# SolderingStation_Control_-_PUMD2.net
KiCad netlist of a schematic drawn in Altium Designer
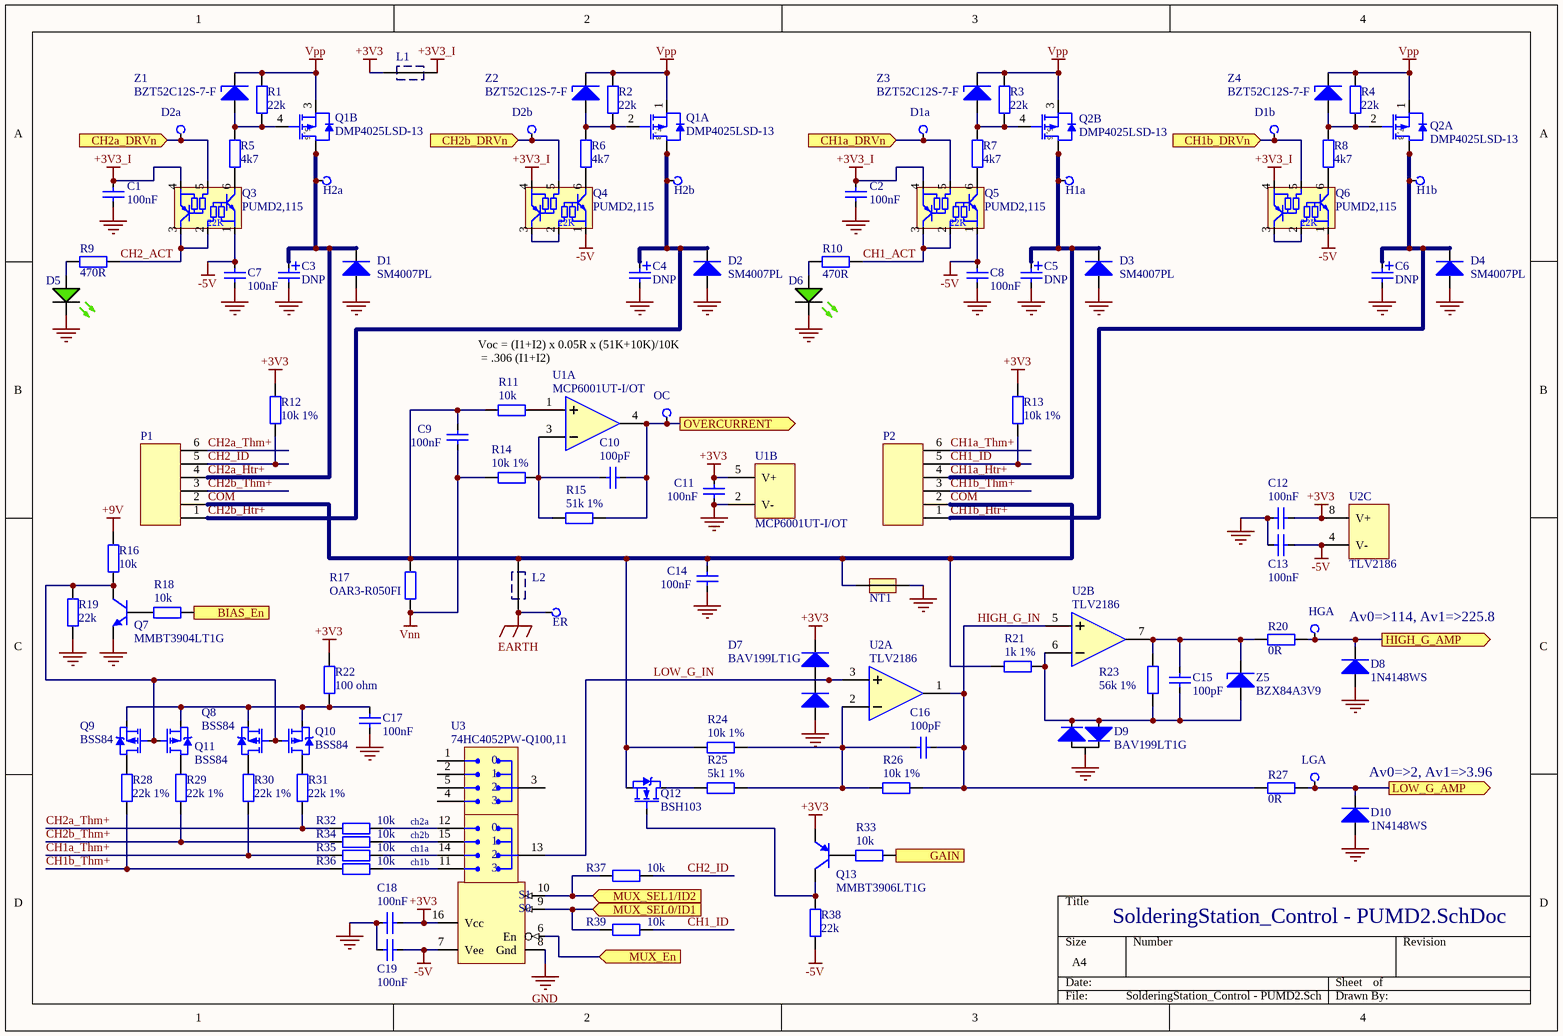
[diagram p0: SolderingStation_Control - PUMD2.SchDoc]

(export (version "E")
  (design (tool "Eeschema 10.0.6"))
  (components
    (comp (ref "C1")
      (value "100nF")
      (footprint "CCNP1608-0603")
      (description "Capacitor non-polar SMT 0603")
      (fields
        (field (name "MANUFACTURER") "Generic Components")
        (field (name "PUBLISHER") "Altium Hobart Technology Centre")
      )
      (libsource (lib "MyLibrary") (part "Cap_CCNP_0603"))
    )
    (comp (ref "C2")
      (value "100nF")
      (footprint "CCNP1608-0603")
      (description "Capacitor non-polar SMT 0603")
      (fields
        (field (name "MANUFACTURER") "Generic Components")
        (field (name "PUBLISHER") "Altium Hobart Technology Centre")
      )
      (libsource (lib "MyLibrary") (part "Cap_CCNP_0603"))
    )
    (comp (ref "C3")
      (value "DNP")
      (footprint "CC2012-0805")
      (description "Capacitor SMT 0805")
      (fields
        (field (name "MANUFACTURER") "Generic Components")
        (field (name "PUBLISHER") "Altium Hobart Technology Centre")
      )
      (libsource (lib "MyLibrary") (part "Cap_CC_0805"))
    )
    (comp (ref "C4")
      (value "DNP")
      (footprint "CC2012-0805")
      (description "Capacitor SMT 0805")
      (fields
        (field (name "MANUFACTURER") "Generic Components")
        (field (name "PUBLISHER") "Altium Hobart Technology Centre")
      )
      (libsource (lib "MyLibrary") (part "Cap_CC_0805"))
    )
    (comp (ref "C5")
      (value "DNP")
      (footprint "CC2012-0805")
      (description "Capacitor SMT 0805")
      (fields
        (field (name "MANUFACTURER") "Generic Components")
        (field (name "PUBLISHER") "Altium Hobart Technology Centre")
      )
      (libsource (lib "MyLibrary") (part "Cap_CC_0805"))
    )
    (comp (ref "C6")
      (value "DNP")
      (footprint "CC2012-0805")
      (description "Capacitor SMT 0805")
      (fields
        (field (name "MANUFACTURER") "Generic Components")
        (field (name "PUBLISHER") "Altium Hobart Technology Centre")
      )
      (libsource (lib "MyLibrary") (part "Cap_CC_0805"))
    )
    (comp (ref "C7")
      (value "100nF")
      (footprint "CCNP1608-0603")
      (description "Capacitor non-polar SMT 0603")
      (fields
        (field (name "MANUFACTURER") "Generic Components")
        (field (name "PUBLISHER") "Altium Hobart Technology Centre")
      )
      (libsource (lib "MyLibrary") (part "Cap_CCNP_0603"))
    )
    (comp (ref "C8")
      (value "100nF")
      (footprint "CCNP1608-0603")
      (description "Capacitor non-polar SMT 0603")
      (fields
        (field (name "MANUFACTURER") "Generic Components")
        (field (name "PUBLISHER") "Altium Hobart Technology Centre")
      )
      (libsource (lib "MyLibrary") (part "Cap_CCNP_0603"))
    )
    (comp (ref "C9")
      (value "100nF")
      (footprint "CCNP1608-0603")
      (description "Capacitor non-polar SMT 0603")
      (fields
        (field (name "MANUFACTURER") "Generic Components")
        (field (name "PUBLISHER") "Altium Hobart Technology Centre")
      )
      (libsource (lib "MyLibrary") (part "Cap_CCNP_0603"))
    )
    (comp (ref "C10")
      (value "100pF")
      (footprint "CCNP1608-0603")
      (description "Capacitor non-polar SMT 0603")
      (fields
        (field (name "MANUFACTURER") "Generic Components")
        (field (name "PUBLISHER") "Altium Hobart Technology Centre")
      )
      (libsource (lib "MyLibrary") (part "Cap_CCNP_0603"))
    )
    (comp (ref "C11")
      (value "100nF")
      (footprint "CCNP1608-0603")
      (description "Capacitor non-polar SMT 0603")
      (fields
        (field (name "MANUFACTURER") "Generic Components")
        (field (name "PUBLISHER") "Altium Hobart Technology Centre")
      )
      (libsource (lib "MyLibrary") (part "Cap_CCNP_0603"))
    )
    (comp (ref "C12")
      (value "100nF")
      (footprint "CCNP1608-0603")
      (description "Capacitor non-polar SMT 0603")
      (fields
        (field (name "MANUFACTURER") "Generic Components")
        (field (name "PUBLISHER") "Altium Hobart Technology Centre")
      )
      (libsource (lib "MyLibrary") (part "Cap_CCNP_0603"))
    )
    (comp (ref "C13")
      (value "100nF")
      (footprint "CCNP1608-0603")
      (description "Capacitor non-polar SMT 0603")
      (fields
        (field (name "MANUFACTURER") "Generic Components")
        (field (name "PUBLISHER") "Altium Hobart Technology Centre")
      )
      (libsource (lib "MyLibrary") (part "Cap_CCNP_0603"))
    )
    (comp (ref "C14")
      (value "100nF")
      (footprint "CCNP1608-0603")
      (description "Capacitor non-polar SMT 0603")
      (fields
        (field (name "MANUFACTURER") "Generic Components")
        (field (name "PUBLISHER") "Altium Hobart Technology Centre")
      )
      (libsource (lib "MyLibrary") (part "Cap_CCNP_0603"))
    )
    (comp (ref "C15")
      (value "100pF")
      (footprint "CCNP1608-0603")
      (description "Capacitor non-polar SMT 0603")
      (fields
        (field (name "MANUFACTURER") "Generic Components")
        (field (name "PUBLISHER") "Altium Hobart Technology Centre")
      )
      (libsource (lib "MyLibrary") (part "Cap_CCNP_0603"))
    )
    (comp (ref "C16")
      (value "100pF")
      (footprint "CCNP1608-0603")
      (description "Capacitor non-polar SMT 0603")
      (fields
        (field (name "MANUFACTURER") "Generic Components")
        (field (name "PUBLISHER") "Altium Hobart Technology Centre")
      )
      (libsource (lib "MyLibrary") (part "Cap_CCNP_0603"))
    )
    (comp (ref "C17")
      (value "100nF")
      (footprint "CCNP1608-0603")
      (description "Capacitor non-polar SMT 0603")
      (fields
        (field (name "MANUFACTURER") "Generic Components")
        (field (name "PUBLISHER") "Altium Hobart Technology Centre")
      )
      (libsource (lib "MyLibrary") (part "Cap_CCNP_0603"))
    )
    (comp (ref "C18")
      (value "100nF")
      (footprint "CCNP1608-0603")
      (description "Capacitor non-polar SMT 0603")
      (fields
        (field (name "MANUFACTURER") "Generic Components")
        (field (name "PUBLISHER") "Altium Hobart Technology Centre")
      )
      (libsource (lib "MyLibrary") (part "Cap_CCNP_0603"))
    )
    (comp (ref "C19")
      (value "100nF")
      (footprint "CCNP1608-0603")
      (description "Capacitor non-polar SMT 0603")
      (fields
        (field (name "MANUFACTURER") "Generic Components")
        (field (name "PUBLISHER") "Altium Hobart Technology Centre")
      )
      (libsource (lib "MyLibrary") (part "Cap_CCNP_0603"))
    )
    (comp (ref "D1")
      (value "SM4007PL")
      (footprint "SOD-123FL")
      (description "Diodes - General Purpose, 1kV 1A 1.1V 1A SOD-123FL")
      (libsource (lib "MyLibrary") (part "SM4007PL"))
    )
    (comp (ref "D1a")
      (value "Drive1")
      (footprint "PCBPIN - 0.7mm")
      (description "Test Point")
      (libsource (lib "MyLibrary") (part "TP"))
    )
    (comp (ref "D1b")
      (value "Drive2")
      (footprint "PCBPIN - 0.7mm")
      (description "Test Point")
      (libsource (lib "MyLibrary") (part "TP"))
    )
    (comp (ref "D2")
      (value "SM4007PL")
      (footprint "SOD-123FL")
      (description "Diodes - General Purpose, 1kV 1A 1.1V 1A SOD-123FL")
      (libsource (lib "MyLibrary") (part "SM4007PL"))
    )
    (comp (ref "D2a")
      (value "Drive2")
      (footprint "PCBPIN - 0.7mm")
      (description "Test Point")
      (libsource (lib "MyLibrary") (part "TP"))
    )
    (comp (ref "D2b")
      (value "Drive2")
      (footprint "PCBPIN - 0.7mm")
      (description "Test Point")
      (libsource (lib "MyLibrary") (part "TP"))
    )
    (comp (ref "D3")
      (value "SM4007PL")
      (footprint "SOD-123FL")
      (description "Diodes - General Purpose, 1kV 1A 1.1V 1A SOD-123FL")
      (libsource (lib "MyLibrary") (part "SM4007PL"))
    )
    (comp (ref "D4")
      (value "SM4007PL")
      (footprint "SOD-123FL")
      (description "Diodes - General Purpose, 1kV 1A 1.1V 1A SOD-123FL")
      (libsource (lib "MyLibrary") (part "SM4007PL"))
    )
    (comp (ref "D5")
      (value "LED")
      (footprint "LED3MM-GREEN - 10mm Proud")
      (description "3mm Green LED")
      (fields (field (name "MANUFACTURER") "Generic Components") (field (name "PUBLISHER") "Altium Limited"))
      (libsource (lib "MySchLib") (part "LED_3MM_GREEN"))
    )
    (comp (ref "D6")
      (value "LED")
      (footprint "LED3MM-GREEN - 10mm Proud")
      (description "3mm Green LED")
      (fields (field (name "MANUFACTURER") "Generic Components") (field (name "PUBLISHER") "Altium Limited"))
      (libsource (lib "MySchLib") (part "LED_3MM_GREEN"))
    )
    (comp (ref "D7")
      (value "BAV199LT1G")
      (footprint "SOT23_M")
      (description "Dual Series low-leakage switching diodes, 3-Pin SOT-23")
      (libsource (lib "MySchLib") (part "BAV199LT1G"))
    )
    (comp (ref "D8")
      (value "1N4148WS")
      (footprint "SOD-323")
      (description "Switching Diode 100V 150mA 1.25V@150mA 4ns SOD-323")
      (libsource (lib "MyLibrary") (part "1N4148WS"))
    )
    (comp (ref "D9")
      (value "BAV199LT1G")
      (footprint "SOT23_M")
      (description "Dual Series low-leakage switching diodes, 3-Pin SOT-23")
      (libsource (lib "MyLibrary") (part "BAV199LT1G"))
    )
    (comp (ref "D10")
      (value "1N4148WS")
      (footprint "SOD-323")
      (description "Switching Diode 100V 150mA 1.25V@150mA 4ns SOD-323")
      (libsource (lib "MyLibrary") (part "1N4148WS"))
    )
    (comp (ref "ER")
      (value "Gnd")
      (footprint "PCBPIN - 1mm")
      (description "Test Point")
      (libsource (lib "") (part "TP_1"))
    )
    (comp (ref "H1a")
      (value "Heater1")
      (footprint "PCBPIN - 0.7mm")
      (description "Test Point")
      (libsource (lib "") (part "TP_1"))
    )
    (comp (ref "H1b")
      (value "Heater2")
      (footprint "PCBPIN - 0.7mm")
      (description "Test Point")
      (libsource (lib "") (part "TP_1"))
    )
    (comp (ref "H2a")
      (value "Heater2")
      (footprint "PCBPIN - 0.7mm")
      (description "Test Point")
      (libsource (lib "") (part "TP_1"))
    )
    (comp (ref "H2b")
      (value "Heater2")
      (footprint "PCBPIN - 0.7mm")
      (description "Test Point")
      (libsource (lib "") (part "TP_1"))
    )
    (comp (ref "HGA")
      (value "TC1")
      (footprint "PCBPIN - 0.7mm")
      (description "Test Point")
      (libsource (lib "MyLibrary") (part "TP"))
    )
    (comp (ref "L1")
      (value "Ferrite Bead")
      (footprint "FB2012-0805")
      (description "Ferrite Bead SMT 0805, TDK MPZ2012S102AT, 0.15OHM, 1.5A")
      (libsource (lib "MySchLib") (part "Ferrite Bead 0805"))
    )
    (comp (ref "L2")
      (value "Ferrite Bead")
      (footprint "FB2012-0805")
      (description "Ferrite Bead SMT 0805, TDK MPZ2012S102AT, 0.15OHM, 1.5A")
      (libsource (lib "MySchLib") (part "Ferrite Bead 0805"))
    )
    (comp (ref "LGA")
      (value "NTC1")
      (footprint "PCBPIN - 0.7mm")
      (description "Test Point")
      (libsource (lib "MyLibrary") (part "TP"))
    )
    (comp (ref "NT1")
      (value "NetTieVia")
      (footprint "NetTieVia")
      (libsource (lib "MyLibrary") (part "NetTieVia"))
    )
    (comp (ref "OC")
      (value "Overcurrent")
      (footprint "PCBPIN - 0.7mm")
      (description "Test Point")
      (libsource (lib "MyLibrary") (part "TP"))
    )
    (comp (ref "P1")
      (value "MOLEX-43045-0612")
      (footprint "MOLEX-43045-0612")
      (description "Wire-To-Board Connector, With Polarizing Peg, 3 mm, 6 Contacts, Header, Micro-Fit 3.0 43045 Series")
      (libsource (lib "MySchLib") (part "MOLEX-43045-0612"))
    )
    (comp (ref "P2")
      (value "MOLEX-43045-0612")
      (footprint "MOLEX-43045-0612")
      (description "Wire-To-Board Connector, With Polarizing Peg, 3 mm, 6 Contacts, Header, Micro-Fit 3.0 43045 Series")
      (libsource (lib "MySchLib") (part "MOLEX-43045-0612"))
    )
    (comp (ref "Q1")
      (value "DMP4025LSD-13")
      (footprint "SO-8_M")
      (description "P-Channel dual MOSFET, 40 V, 7.6 A, 0.018 ohm, SOIC, Surface Mount")
      (libsource (lib "MyLibrary") (part "DMP4025LSD-13"))
    )
    (comp (ref "Q2")
      (value "DMP4025LSD-13")
      (footprint "SO-8_M")
      (description "P-Channel dual MOSFET, 40 V, 7.6 A, 0.018 ohm, SOIC, Surface Mount")
      (libsource (lib "MyLibrary") (part "DMP4025LSD-13"))
    )
    (comp (ref "Q3")
      (value "PUMD2,115")
      (footprint "SOT363-6M")
      (description "Pre-Biased NPN and PNP pair, 50 V, 100 mA, 22 kohm, 22 kohm")
      (libsource (lib "MySchLib") (part "PUMD2,115"))
    )
    (comp (ref "Q4")
      (value "PUMD2,115")
      (footprint "SOT363-6M")
      (description "Pre-Biased NPN and PNP pair, 50 V, 100 mA, 22 kohm, 22 kohm")
      (libsource (lib "MySchLib") (part "PUMD2,115"))
    )
    (comp (ref "Q5")
      (value "PUMD2,115")
      (footprint "SOT363-6M")
      (description "Pre-Biased NPN and PNP pair, 50 V, 100 mA, 22 kohm, 22 kohm")
      (libsource (lib "MySchLib") (part "PUMD2,115"))
    )
    (comp (ref "Q6")
      (value "PUMD2,115")
      (footprint "SOT363-6M")
      (description "Pre-Biased NPN and PNP pair, 50 V, 100 mA, 22 kohm, 22 kohm")
      (libsource (lib "MySchLib") (part "PUMD2,115"))
    )
    (comp (ref "Q7")
      (value "MMBT3904LT1G")
      (footprint "SOT23_N")
      (description "General Purpose Transistor, NPN Silicon, 3-Pin SOT-23, Pb-Free, Tape and Reel")
      (fields (field (name "MANUFACTURER") "On Semiconductor"))
      (libsource (lib "MyLibrary") (part "MMBT3904LT1G"))
    )
    (comp (ref "Q8")
      (value "BSS84")
      (footprint "SOT23_M")
      (description "P-Channel Enhancement Mode FET -0.13 A, -50 V,  RDS(ON) = 10R at VGS = -5 V")
      (libsource (lib "MySchLib") (part "BSS84"))
    )
    (comp (ref "Q9")
      (value "BSS84")
      (footprint "SOT23_M")
      (description "P-Channel Enhancement Mode FET -0.13 A, -50 V,  RDS(ON) = 10R at VGS = -5 V")
      (libsource (lib "MySchLib") (part "BSS84"))
    )
    (comp (ref "Q10")
      (value "BSS84")
      (footprint "SOT23_M")
      (description "P-Channel Enhancement Mode FET -0.13 A, -50 V,  RDS(ON) = 10R at VGS = -5 V")
      (libsource (lib "MySchLib") (part "BSS84"))
    )
    (comp (ref "Q11")
      (value "BSS84")
      (footprint "SOT23_M")
      (description "P-Channel Enhancement Mode FET -0.13 A, -50 V,  RDS(ON) = 10R at VGS = -5 V")
      (libsource (lib "MySchLib") (part "BSS84"))
    )
    (comp (ref "Q12")
      (value "BSH103")
      (footprint "SOT23_N")
      (description "N-channel enhancement mode FET, , 30 V, 850 mA, 0.4 ohm, SOT23")
      (libsource (lib "MyLibrary") (part "BSH103"))
    )
    (comp (ref "Q13")
      (value "MMBT3906LT1G")
      (footprint "SOT23_N")
      (description "General Purpose Transistor, PNP Silicon, 3-Pin SOT-23, Pb-Free, Tape and Reel")
      (fields (field (name "MANUFACTURER") "On Semiconductor"))
      (libsource (lib "MyLibrary") (part "MMBT3906LT1G"))
    )
    (comp (ref "R1")
      (value "22k")
      (footprint "CR1608-0603_N")
      (description "Resistor SMT 0603")
      (fields
        (field (name "MANUFACTURER") "Generic Components")
        (field (name "PUBLISHER") "Altium Hobart Technology Centre")
      )
      (libsource (lib "MyLibrary") (part "Res_CR0603"))
    )
    (comp (ref "R2")
      (value "22k")
      (footprint "CR1608-0603_N")
      (description "Resistor SMT 0603")
      (fields
        (field (name "MANUFACTURER") "Generic Components")
        (field (name "PUBLISHER") "Altium Hobart Technology Centre")
      )
      (libsource (lib "MyLibrary") (part "Res_CR0603"))
    )
    (comp (ref "R3")
      (value "22k")
      (footprint "CR1608-0603_N")
      (description "Resistor SMT 0603")
      (fields
        (field (name "MANUFACTURER") "Generic Components")
        (field (name "PUBLISHER") "Altium Hobart Technology Centre")
      )
      (libsource (lib "MyLibrary") (part "Res_CR0603"))
    )
    (comp (ref "R4")
      (value "22k")
      (footprint "CR1608-0603_N")
      (description "Resistor SMT 0603")
      (fields
        (field (name "MANUFACTURER") "Generic Components")
        (field (name "PUBLISHER") "Altium Hobart Technology Centre")
      )
      (libsource (lib "MyLibrary") (part "Res_CR0603"))
    )
    (comp (ref "R5")
      (value "4k7")
      (footprint "CR1608-0603_N")
      (description "Resistor SMT 0603")
      (fields
        (field (name "MANUFACTURER") "Generic Components")
        (field (name "PUBLISHER") "Altium Hobart Technology Centre")
      )
      (libsource (lib "MyLibrary") (part "Res_CR0603"))
    )
    (comp (ref "R6")
      (value "4k7")
      (footprint "CR1608-0603_N")
      (description "Resistor SMT 0603")
      (fields
        (field (name "MANUFACTURER") "Generic Components")
        (field (name "PUBLISHER") "Altium Hobart Technology Centre")
      )
      (libsource (lib "MyLibrary") (part "Res_CR0603"))
    )
    (comp (ref "R7")
      (value "4k7")
      (footprint "CR1608-0603_N")
      (description "Resistor SMT 0603")
      (fields
        (field (name "MANUFACTURER") "Generic Components")
        (field (name "PUBLISHER") "Altium Hobart Technology Centre")
      )
      (libsource (lib "MyLibrary") (part "Res_CR0603"))
    )
    (comp (ref "R8")
      (value "4k7")
      (footprint "CR1608-0603_N")
      (description "Resistor SMT 0603")
      (fields
        (field (name "MANUFACTURER") "Generic Components")
        (field (name "PUBLISHER") "Altium Hobart Technology Centre")
      )
      (libsource (lib "MyLibrary") (part "Res_CR0603"))
    )
    (comp (ref "R9")
      (value "470R")
      (footprint "CR1608-0603_N")
      (description "Resistor SMT 0603")
      (fields
        (field (name "MANUFACTURER") "Generic Components")
        (field (name "PUBLISHER") "Altium Hobart Technology Centre")
      )
      (libsource (lib "") (part "Res_CR0603_3"))
    )
    (comp (ref "R10")
      (value "470R")
      (footprint "CR1608-0603_N")
      (description "Resistor SMT 0603")
      (fields
        (field (name "MANUFACTURER") "Generic Components")
        (field (name "PUBLISHER") "Altium Hobart Technology Centre")
      )
      (libsource (lib "") (part "Res_CR0603_3"))
    )
    (comp (ref "R11")
      (value "10k")
      (footprint "CR1608-0603_N")
      (description "Resistor SMT 0603")
      (fields
        (field (name "MANUFACTURER") "Generic Components")
        (field (name "PUBLISHER") "Altium Hobart Technology Centre")
      )
      (libsource (lib "") (part "Res_CR0603_2"))
    )
    (comp (ref "R12")
      (value "10k 1%")
      (footprint "CR1608-0603_N")
      (description "Resistor SMT 0603")
      (fields
        (field (name "MANUFACTURER") "Generic Components")
        (field (name "PUBLISHER") "Altium Hobart Technology Centre")
      )
      (libsource (lib "MyLibrary") (part "Res_CR0603"))
    )
    (comp (ref "R13")
      (value "10k 1%")
      (footprint "CR1608-0603_N")
      (description "Resistor SMT 0603")
      (fields
        (field (name "MANUFACTURER") "Generic Components")
        (field (name "PUBLISHER") "Altium Hobart Technology Centre")
      )
      (libsource (lib "MyLibrary") (part "Res_CR0603"))
    )
    (comp (ref "R14")
      (value "10k 1%")
      (footprint "CR1608-0603_N")
      (description "Resistor SMT 0603")
      (fields
        (field (name "MANUFACTURER") "Generic Components")
        (field (name "PUBLISHER") "Altium Hobart Technology Centre")
      )
      (libsource (lib "") (part "Res_CR0603_2"))
    )
    (comp (ref "R15")
      (value "51k 1%")
      (footprint "CR1608-0603_N")
      (description "Resistor SMT 0603")
      (fields
        (field (name "MANUFACTURER") "Generic Components")
        (field (name "PUBLISHER") "Altium Hobart Technology Centre")
      )
      (libsource (lib "") (part "Res_CR0603_3"))
    )
    (comp (ref "R16")
      (value "10k")
      (footprint "CR1608-0603_N")
      (description "Resistor SMT 0603")
      (fields
        (field (name "MANUFACTURER") "Generic Components")
        (field (name "PUBLISHER") "Altium Hobart Technology Centre")
      )
      (libsource (lib "") (part "Res_CR0603_1"))
    )
    (comp (ref "R17")
      (value "OAR3-R050FI")
      (footprint "OAR3-R050FI")
      (description "Current Sense Resistor, 0.05 ohm, OAR Series, 3 W, Metal Strip, Radial Leaded, 1%")
      (libsource (lib "MySchLib") (part "OAR3-R050FI"))
    )
    (comp (ref "R18")
      (value "10k")
      (footprint "CR1608-0603_N")
      (description "Resistor SMT 0603")
      (fields
        (field (name "MANUFACTURER") "Generic Components")
        (field (name "PUBLISHER") "Altium Hobart Technology Centre")
      )
      (libsource (lib "") (part "Res_CR0603_3"))
    )
    (comp (ref "R19")
      (value "22k")
      (footprint "CR1608-0603_N")
      (description "Resistor SMT 0603")
      (fields
        (field (name "MANUFACTURER") "Generic Components")
        (field (name "PUBLISHER") "Altium Hobart Technology Centre")
      )
      (libsource (lib "MyLibrary") (part "Res_CR0603"))
    )
    (comp (ref "R20")
      (value "0R")
      (footprint "CR1608-0603_N")
      (description "Resistor SMT 0603")
      (fields
        (field (name "MANUFACTURER") "Generic Components")
        (field (name "PUBLISHER") "Altium Hobart Technology Centre")
      )
      (libsource (lib "") (part "Res_CR0603_1"))
    )
    (comp (ref "R21")
      (value "1k 1%")
      (footprint "CR1608-0603_N")
      (description "Resistor SMT 0603")
      (fields
        (field (name "MANUFACTURER") "Generic Components")
        (field (name "PUBLISHER") "Altium Hobart Technology Centre")
      )
      (libsource (lib "") (part "Res_CR0603_2"))
    )
    (comp (ref "R22")
      (value "100 ohm")
      (footprint "CR1608-0603_N")
      (description "Resistor SMT 0603")
      (fields
        (field (name "MANUFACTURER") "Generic Components")
        (field (name "PUBLISHER") "Altium Hobart Technology Centre")
      )
      (libsource (lib "") (part "Res_CR0603_2"))
    )
    (comp (ref "R23")
      (value "56k 1%")
      (footprint "CR1608-0603_N")
      (description "Resistor SMT 0603")
      (fields
        (field (name "MANUFACTURER") "Generic Components")
        (field (name "PUBLISHER") "Altium Hobart Technology Centre")
      )
      (libsource (lib "MyLibrary") (part "Res_CR0603"))
    )
    (comp (ref "R24")
      (value "10k 1%")
      (footprint "CR1608-0603_N")
      (description "Resistor SMT 0603")
      (fields
        (field (name "MANUFACTURER") "Generic Components")
        (field (name "PUBLISHER") "Altium Hobart Technology Centre")
      )
      (libsource (lib "") (part "Res_CR0603_3"))
    )
    (comp (ref "R25")
      (value "5k1 1%")
      (footprint "CR1608-0603_N")
      (description "Resistor SMT 0603")
      (fields
        (field (name "MANUFACTURER") "Generic Components")
        (field (name "PUBLISHER") "Altium Hobart Technology Centre")
      )
      (libsource (lib "") (part "Res_CR0603_1"))
    )
    (comp (ref "R26")
      (value "10k 1%")
      (footprint "CR1608-0603_N")
      (description "Resistor SMT 0603")
      (fields
        (field (name "MANUFACTURER") "Generic Components")
        (field (name "PUBLISHER") "Altium Hobart Technology Centre")
      )
      (libsource (lib "") (part "Res_CR0603_3"))
    )
    (comp (ref "R27")
      (value "0R")
      (footprint "CR1608-0603_N")
      (description "Resistor SMT 0603")
      (fields
        (field (name "MANUFACTURER") "Generic Components")
        (field (name "PUBLISHER") "Altium Hobart Technology Centre")
      )
      (libsource (lib "") (part "Res_CR0603_1"))
    )
    (comp (ref "R28")
      (value "22k 1%")
      (footprint "CR1608-0603_N")
      (description "Resistor SMT 0603")
      (fields
        (field (name "MANUFACTURER") "Generic Components")
        (field (name "PUBLISHER") "Altium Hobart Technology Centre")
      )
      (libsource (lib "") (part "Res_CR0603_3"))
    )
    (comp (ref "R29")
      (value "22k 1%")
      (footprint "CR1608-0603_N")
      (description "Resistor SMT 0603")
      (fields
        (field (name "MANUFACTURER") "Generic Components")
        (field (name "PUBLISHER") "Altium Hobart Technology Centre")
      )
      (libsource (lib "") (part "Res_CR0603_3"))
    )
    (comp (ref "R30")
      (value "22k 1%")
      (footprint "CR1608-0603_N")
      (description "Resistor SMT 0603")
      (fields
        (field (name "MANUFACTURER") "Generic Components")
        (field (name "PUBLISHER") "Altium Hobart Technology Centre")
      )
      (libsource (lib "MyLibrary") (part "Res_CR0603"))
    )
    (comp (ref "R31")
      (value "22k 1%")
      (footprint "CR1608-0603_N")
      (description "Resistor SMT 0603")
      (fields
        (field (name "MANUFACTURER") "Generic Components")
        (field (name "PUBLISHER") "Altium Hobart Technology Centre")
      )
      (libsource (lib "MyLibrary") (part "Res_CR0603"))
    )
    (comp (ref "R32")
      (value "10k")
      (footprint "CR1608-0603_N")
      (description "Resistor SMT 0603")
      (fields
        (field (name "MANUFACTURER") "Generic Components")
        (field (name "PUBLISHER") "Altium Hobart Technology Centre")
      )
      (libsource (lib "") (part "Res_CR0603_1"))
    )
    (comp (ref "R33")
      (value "10k")
      (footprint "CR1608-0603_N")
      (description "Resistor SMT 0603")
      (fields
        (field (name "MANUFACTURER") "Generic Components")
        (field (name "PUBLISHER") "Altium Hobart Technology Centre")
      )
      (libsource (lib "") (part "Res_CR0603_3"))
    )
    (comp (ref "R34")
      (value "10k")
      (footprint "CR1608-0603_N")
      (description "Resistor SMT 0603")
      (fields
        (field (name "MANUFACTURER") "Generic Components")
        (field (name "PUBLISHER") "Altium Hobart Technology Centre")
      )
      (libsource (lib "") (part "Res_CR0603_1"))
    )
    (comp (ref "R35")
      (value "10k")
      (footprint "CR1608-0603_N")
      (description "Resistor SMT 0603")
      (fields
        (field (name "MANUFACTURER") "Generic Components")
        (field (name "PUBLISHER") "Altium Hobart Technology Centre")
      )
      (libsource (lib "") (part "Res_CR0603_1"))
    )
    (comp (ref "R36")
      (value "10k")
      (footprint "CR1608-0603_N")
      (description "Resistor SMT 0603")
      (fields
        (field (name "MANUFACTURER") "Generic Components")
        (field (name "PUBLISHER") "Altium Hobart Technology Centre")
      )
      (libsource (lib "") (part "Res_CR0603_1"))
    )
    (comp (ref "R37")
      (value "10k")
      (footprint "CR1608-0603_N")
      (description "Resistor SMT 0603")
      (fields
        (field (name "MANUFACTURER") "Generic Components")
        (field (name "PUBLISHER") "Altium Hobart Technology Centre")
      )
      (libsource (lib "") (part "Res_CR0603_1"))
    )
    (comp (ref "R38")
      (value "22k")
      (footprint "CR1608-0603_N")
      (description "Resistor SMT 0603")
      (fields
        (field (name "MANUFACTURER") "Generic Components")
        (field (name "PUBLISHER") "Altium Hobart Technology Centre")
      )
      (libsource (lib "MyLibrary") (part "Res_CR0603"))
    )
    (comp (ref "R39")
      (value "10k")
      (footprint "CR1608-0603_N")
      (description "Resistor SMT 0603")
      (fields
        (field (name "MANUFACTURER") "Generic Components")
        (field (name "PUBLISHER") "Altium Hobart Technology Centre")
      )
      (libsource (lib "") (part "Res_CR0603_1"))
    )
    (comp (ref "U1")
      (value "MCP6001UT-I/OT")
      (footprint "SOT23-5_M")
      (description "Op-Amp, Single supply R-R in/out")
      (libsource (lib "MySchLib") (part "MCP6001UT-I/OT"))
    )
    (comp (ref "U2")
      (value "TLV2186")
      (footprint "SOIC127P600-8M")
      (description "Dual Precision,Rail-to-Rail Input and Output, 4.5-24V, Zero-Drift OperationalAmplifier")
      (libsource (lib "MySchLib") (part "TLV2186"))
    )
    (comp (ref "U3")
      (value "74HC4052PW-Q100,11")
      (footprint "TSSOP16_M")
      (description "Analog Multiplexer / Demultiplexer, 4:1, 2 Circuits, 225 ohm, 2V to 10V, TSSOP-16")
      (libsource (lib "MySchLib") (part "74HC4052PW-Q100,11"))
    )
    (comp (ref "Z1")
      (value "BZT52C12S-7-F")
      (footprint "SOD-323")
      (description "Surface Mount Zener Diode, 12-13 V, -65 to 150 degC, SOD-123")
      (libsource (lib "MySchLib") (part "BZT52C12S-7-F"))
    )
    (comp (ref "Z2")
      (value "BZT52C12S-7-F")
      (footprint "SOD-323")
      (description "Surface Mount Zener Diode, 12-13 V, -65 to 150 degC, SOD-123")
      (libsource (lib "MySchLib") (part "BZT52C12S-7-F"))
    )
    (comp (ref "Z3")
      (value "BZT52C12S-7-F")
      (footprint "SOD-323")
      (description "Surface Mount Zener Diode, 12-13 V, -65 to 150 degC, SOD-123")
      (libsource (lib "MySchLib") (part "BZT52C12S-7-F"))
    )
    (comp (ref "Z4")
      (value "BZT52C12S-7-F")
      (footprint "SOD-323")
      (description "Surface Mount Zener Diode, 12-13 V, -65 to 150 degC, SOD-123")
      (libsource (lib "MySchLib") (part "BZT52C12S-7-F"))
    )
    (comp (ref "Z5")
      (value "BZX84A3V9")
      (footprint "SOT23_M")
      (description "Zener Diode, 3.9V, 250mW, SOT-23, 1%, 150C")
      (fields
        (field (name "MANUFACTURER") "Generic Components")
        (field (name "PUBLISHER") "Altium Hobart Technology Centre")
      )
      (libsource (lib "MyLibrary") (part "BZX84A3V9"))
    )
  )
  (nets
    (net (code "1") (name "+3V3") (class "Default")
      (node (ref "C11") (pin "1") (pinfunction "1_1") (pintype "passive"))
      (node (ref "C12") (pin "1") (pinfunction "1_1") (pintype "passive"))
      (node (ref "C18") (pin "1") (pinfunction "1_1") (pintype "passive"))
      (node (ref "D7") (pin "2") (pinfunction "A2_2") (pintype "passive"))
      (node (ref "L1") (pin "1") (pinfunction "1_1") (pintype "passive"))
      (node (ref "Q13") (pin "2") (pinfunction "E_2") (pintype "passive"))
      (node (ref "R12") (pin "2") (pinfunction "2_2") (pintype "passive"))
      (node (ref "R13") (pin "2") (pinfunction "2_2") (pintype "passive"))
      (node (ref "R22") (pin "1") (pinfunction "1_1") (pintype "passive"))
      (node (ref "U1") (pin "5") (pinfunction "V+_5") (pintype "power_in"))
      (node (ref "U2") (pin "8") (pinfunction "V+_8") (pintype "power_in"))
      (node (ref "U3") (pin "16") (pinfunction "Vcc_16") (pintype "power_in"))
    )
    (net (code "2") (name "+3V3_I") (class "Default")
      (node (ref "C1") (pin "1") (pinfunction "1_1") (pintype "passive"))
      (node (ref "C2") (pin "1") (pinfunction "1_1") (pintype "passive"))
      (node (ref "L1") (pin "2") (pinfunction "2_2") (pintype "passive"))
      (node (ref "Q3") (pin "4") (pinfunction "E2_4") (pintype "passive"))
      (node (ref "Q4") (pin "4") (pinfunction "E2_4") (pintype "passive"))
      (node (ref "Q5") (pin "4") (pinfunction "E2_4") (pintype "passive"))
      (node (ref "Q6") (pin "4") (pinfunction "E2_4") (pintype "passive"))
    )
    (net (code "3") (name "+9V") (class "Default")
      (node (ref "R16") (pin "1") (pinfunction "1_1") (pintype "passive"))
    )
    (net (code "4") (name "-5V") (class "Default")
      (node (ref "C13") (pin "1") (pinfunction "1_1") (pintype "passive"))
      (node (ref "C19") (pin "1") (pinfunction "1_1") (pintype "passive"))
      (node (ref "C7") (pin "1") (pinfunction "1_1") (pintype "passive"))
      (node (ref "C8") (pin "1") (pinfunction "1_1") (pintype "passive"))
      (node (ref "Q3") (pin "1") (pinfunction "E1_1") (pintype "passive"))
      (node (ref "Q4") (pin "1") (pinfunction "E1_1") (pintype "passive"))
      (node (ref "Q5") (pin "1") (pinfunction "E1_1") (pintype "passive"))
      (node (ref "Q6") (pin "1") (pinfunction "E1_1") (pintype "passive"))
      (node (ref "R38") (pin "1") (pinfunction "1_1") (pintype "passive"))
      (node (ref "U2") (pin "4") (pinfunction "V-_4") (pintype "power_in"))
      (node (ref "U3") (pin "7") (pinfunction "Vee_7") (pintype "power_in"))
    )
    (net (code "5") (name "/BIAS_En") (class "Default")
      (node (ref "R18") (pin "2") (pinfunction "2_2") (pintype "passive"))
    )
    (net (code "6") (name "/CH1_ACT") (class "Default")
      (node (ref "Q5") (pin "2") (pinfunction "B1_2") (pintype "passive"))
      (node (ref "Q5") (pin "3") (pinfunction "C2_3") (pintype "passive"))
      (node (ref "R10") (pin "2") (pinfunction "2_2") (pintype "passive"))
    )
    (net (code "7") (name "/CH1_ID") (class "Default")
      (node (ref "P2") (pin "5") (pinfunction "5_5") (pintype "passive"))
      (node (ref "R13") (pin "1") (pinfunction "1_1") (pintype "passive"))
      (node (ref "R39") (pin "1") (pinfunction "1_1") (pintype "passive"))
    )
    (net (code "8") (name "/CH1a_DRVn") (class "Default")
      (node (ref "D1a") (pin "1") (pinfunction "TP_1") (pintype "passive"))
      (node (ref "Q5") (pin "5") (pinfunction "B2_5") (pintype "passive"))
    )
    (net (code "9") (name "/CH1a_Htr+") (class "Default")
      (node (ref "C5") (pin "1") (pinfunction "1_1") (pintype "passive"))
      (node (ref "D3") (pin "K") (pinfunction "K_K") (pintype "passive"))
      (node (ref "H1a") (pin "1") (pinfunction "TP_1") (pintype "passive"))
      (node (ref "P2") (pin "4") (pinfunction "4_4") (pintype "passive"))
      (node (ref "Q2") (pin "5") (pinfunction "D2_5") (pintype "passive"))
      (node (ref "Q2") (pin "6") (pinfunction "D2_6") (pintype "passive"))
    )
    (net (code "10") (name "/CH1a_Thm+") (class "Default")
      (node (ref "P2") (pin "6") (pinfunction "6_6") (pintype "passive"))
      (node (ref "R30") (pin "1") (pinfunction "1_1") (pintype "passive"))
      (node (ref "R35") (pin "2") (pinfunction "2_2") (pintype "passive"))
    )
    (net (code "11") (name "/CH1b_DRVn") (class "Default")
      (node (ref "D1b") (pin "1") (pinfunction "TP_1") (pintype "passive"))
      (node (ref "Q6") (pin "5") (pinfunction "B2_5") (pintype "passive"))
    )
    (net (code "12") (name "/CH1b_Htr+") (class "Default")
      (node (ref "C6") (pin "1") (pinfunction "1_1") (pintype "passive"))
      (node (ref "D4") (pin "K") (pinfunction "K_K") (pintype "passive"))
      (node (ref "H1b") (pin "1") (pinfunction "TP_1") (pintype "passive"))
      (node (ref "P2") (pin "1") (pinfunction "1_1") (pintype "passive"))
      (node (ref "Q2") (pin "7") (pinfunction "D1_7") (pintype "passive"))
      (node (ref "Q2") (pin "8") (pinfunction "D1_8") (pintype "passive"))
    )
    (net (code "13") (name "/CH1b_Thm+") (class "Default")
      (node (ref "P2") (pin "3") (pinfunction "3_3") (pintype "passive"))
      (node (ref "R28") (pin "1") (pinfunction "1_1") (pintype "passive"))
      (node (ref "R36") (pin "2") (pinfunction "2_2") (pintype "passive"))
    )
    (net (code "14") (name "/CH2_ACT") (class "Default")
      (node (ref "Q3") (pin "2") (pinfunction "B1_2") (pintype "passive"))
      (node (ref "Q3") (pin "3") (pinfunction "C2_3") (pintype "passive"))
      (node (ref "R9") (pin "2") (pinfunction "2_2") (pintype "passive"))
    )
    (net (code "15") (name "/CH2_ID") (class "Default")
      (node (ref "P1") (pin "5") (pinfunction "5_5") (pintype "passive"))
      (node (ref "R12") (pin "1") (pinfunction "1_1") (pintype "passive"))
      (node (ref "R37") (pin "1") (pinfunction "1_1") (pintype "passive"))
    )
    (net (code "16") (name "/CH2a_DRVn") (class "Default")
      (node (ref "D2a") (pin "1") (pinfunction "TP_1") (pintype "passive"))
      (node (ref "Q3") (pin "5") (pinfunction "B2_5") (pintype "passive"))
    )
    (net (code "17") (name "/CH2a_Htr+") (class "Default")
      (node (ref "C3") (pin "1") (pinfunction "1_1") (pintype "passive"))
      (node (ref "D1") (pin "K") (pinfunction "K_K") (pintype "passive"))
      (node (ref "H2a") (pin "1") (pinfunction "TP_1") (pintype "passive"))
      (node (ref "P1") (pin "4") (pinfunction "4_4") (pintype "passive"))
      (node (ref "Q1") (pin "5") (pinfunction "D2_5") (pintype "passive"))
      (node (ref "Q1") (pin "6") (pinfunction "D2_6") (pintype "passive"))
    )
    (net (code "18") (name "/CH2a_Thm+") (class "Default")
      (node (ref "P1") (pin "6") (pinfunction "6_6") (pintype "passive"))
      (node (ref "R31") (pin "1") (pinfunction "1_1") (pintype "passive"))
      (node (ref "R32") (pin "2") (pinfunction "2_2") (pintype "passive"))
    )
    (net (code "19") (name "/CH2b_DRVn") (class "Default")
      (node (ref "D2b") (pin "1") (pinfunction "TP_1") (pintype "passive"))
      (node (ref "Q4") (pin "5") (pinfunction "B2_5") (pintype "passive"))
    )
    (net (code "20") (name "/CH2b_Htr+") (class "Default")
      (node (ref "C4") (pin "1") (pinfunction "1_1") (pintype "passive"))
      (node (ref "D2") (pin "K") (pinfunction "K_K") (pintype "passive"))
      (node (ref "H2b") (pin "1") (pinfunction "TP_1") (pintype "passive"))
      (node (ref "P1") (pin "1") (pinfunction "1_1") (pintype "passive"))
      (node (ref "Q1") (pin "7") (pinfunction "D1_7") (pintype "passive"))
      (node (ref "Q1") (pin "8") (pinfunction "D1_8") (pintype "passive"))
    )
    (net (code "21") (name "/CH2b_Thm+") (class "Default")
      (node (ref "P1") (pin "3") (pinfunction "3_3") (pintype "passive"))
      (node (ref "R29") (pin "1") (pinfunction "1_1") (pintype "passive"))
      (node (ref "R34") (pin "2") (pinfunction "2_2") (pintype "passive"))
    )
    (net (code "22") (name "/COM") (class "Default")
      (node (ref "C14") (pin "1") (pinfunction "1_1") (pintype "passive"))
      (node (ref "C9") (pin "1") (pinfunction "1_1") (pintype "passive"))
      (node (ref "L2") (pin "2") (pinfunction "2_2") (pintype "passive"))
      (node (ref "NT1") (pin "2") (pinfunction "2_2") (pintype "passive"))
      (node (ref "P1") (pin "2") (pinfunction "2_2") (pintype "passive"))
      (node (ref "P2") (pin "2") (pinfunction "2_2") (pintype "passive"))
      (node (ref "Q12") (pin "2") (pinfunction "S_2") (pintype "passive"))
      (node (ref "R11") (pin "2") (pinfunction "2_2") (pintype "passive"))
      (node (ref "R17") (pin "2") (pinfunction "2_2") (pintype "passive"))
      (node (ref "R21") (pin "2") (pinfunction "2_2") (pintype "passive"))
      (node (ref "R24") (pin "1") (pinfunction "1_1") (pintype "passive"))
    )
    (net (code "23") (name "/GAIN") (class "Default")
      (node (ref "R33") (pin "2") (pinfunction "2_2") (pintype "passive"))
    )
    (net (code "24") (name "/HIGH_G_AMP") (class "Default")
      (node (ref "D8") (pin "K") (pinfunction "K_K") (pintype "passive"))
      (node (ref "HGA") (pin "1") (pinfunction "TP_1") (pintype "passive"))
      (node (ref "R20") (pin "1") (pinfunction "1_1") (pintype "passive"))
    )
    (net (code "25") (name "/HIGH_G_IN") (class "Default")
      (node (ref "C16") (pin "2") (pinfunction "2_2") (pintype "passive"))
      (node (ref "R26") (pin "2") (pinfunction "2_2") (pintype "passive"))
      (node (ref "R27") (pin "2") (pinfunction "2_2") (pintype "passive"))
      (node (ref "U2") (pin "1") (pinfunction "A_1") (pintype "passive"))
      (node (ref "U2") (pin "5") (pinfunction "B+_5") (pintype "passive"))
    )
    (net (code "26") (name "/LOW_G_AMP") (class "Default")
      (node (ref "D10") (pin "K") (pinfunction "K_K") (pintype "passive"))
      (node (ref "LGA") (pin "1") (pinfunction "TP_1") (pintype "passive"))
      (node (ref "R27") (pin "1") (pinfunction "1_1") (pintype "passive"))
    )
    (net (code "27") (name "/LOW_G_IN") (class "Default")
      (node (ref "D7") (pin "3") (pinfunction "K_3") (pintype "passive"))
      (node (ref "U2") (pin "3") (pinfunction "A+_3") (pintype "passive"))
      (node (ref "U3") (pin "13") (pinfunction "1Z_13") (pintype "passive"))
    )
    (net (code "28") (name "/MUX_En") (class "Default")
      (node (ref "U3") (pin "6") (pinfunction "En_6") (pintype "input"))
    )
    (net (code "29") (name "/MUX_SEL0{slash}ID1") (class "Default")
      (node (ref "R39") (pin "2") (pinfunction "2_2") (pintype "passive"))
      (node (ref "U3") (pin "9") (pinfunction "S1_9") (pintype "input"))
    )
    (net (code "30") (name "/MUX_SEL1{slash}ID2") (class "Default")
      (node (ref "R37") (pin "2") (pinfunction "2_2") (pintype "passive"))
      (node (ref "U3") (pin "10") (pinfunction "S0_10") (pintype "input"))
    )
    (net (code "31") (name "/OVERCURRENT") (class "Default")
      (node (ref "C10") (pin "2") (pinfunction "2_2") (pintype "passive"))
      (node (ref "OC") (pin "1") (pinfunction "TP_1") (pintype "passive"))
      (node (ref "R15") (pin "2") (pinfunction "2_2") (pintype "passive"))
      (node (ref "U1") (pin "4") (pinfunction "Out_4") (pintype "passive"))
    )
    (net (code "32") (name "EARTH") (class "Default")
      (node (ref "ER") (pin "1") (pinfunction "TP_1") (pintype "passive"))
      (node (ref "L2") (pin "1") (pinfunction "1_1") (pintype "passive"))
    )
    (net (code "33") (name "GND") (class "Default")
      (node (ref "C1") (pin "2") (pinfunction "2_2") (pintype "passive"))
      (node (ref "C11") (pin "2") (pinfunction "2_2") (pintype "passive"))
      (node (ref "C12") (pin "2") (pinfunction "2_2") (pintype "passive"))
      (node (ref "C13") (pin "2") (pinfunction "2_2") (pintype "passive"))
      (node (ref "C14") (pin "2") (pinfunction "2_2") (pintype "passive"))
      (node (ref "C17") (pin "1") (pinfunction "1_1") (pintype "passive"))
      (node (ref "C18") (pin "2") (pinfunction "2_2") (pintype "passive"))
      (node (ref "C19") (pin "2") (pinfunction "2_2") (pintype "passive"))
      (node (ref "C2") (pin "2") (pinfunction "2_2") (pintype "passive"))
      (node (ref "C3") (pin "2") (pinfunction "2_2") (pintype "passive"))
      (node (ref "C4") (pin "2") (pinfunction "2_2") (pintype "passive"))
      (node (ref "C5") (pin "2") (pinfunction "2_2") (pintype "passive"))
      (node (ref "C6") (pin "2") (pinfunction "2_2") (pintype "passive"))
      (node (ref "C7") (pin "2") (pinfunction "2_2") (pintype "passive"))
      (node (ref "C8") (pin "2") (pinfunction "2_2") (pintype "passive"))
      (node (ref "D1") (pin "A") (pinfunction "A_A") (pintype "passive"))
      (node (ref "D10") (pin "A") (pinfunction "A_A") (pintype "passive"))
      (node (ref "D2") (pin "A") (pinfunction "A_A") (pintype "passive"))
      (node (ref "D3") (pin "A") (pinfunction "A_A") (pintype "passive"))
      (node (ref "D4") (pin "A") (pinfunction "A_A") (pintype "passive"))
      (node (ref "D5") (pin "K") (pinfunction "K_K") (pintype "passive"))
      (node (ref "D6") (pin "K") (pinfunction "K_K") (pintype "passive"))
      (node (ref "D7") (pin "1") (pinfunction "A1_1") (pintype "passive"))
      (node (ref "D8") (pin "A") (pinfunction "A_A") (pintype "passive"))
      (node (ref "D9") (pin "3") (pinfunction "K_3") (pintype "passive"))
      (node (ref "NT1") (pin "1") (pinfunction "1_1") (pintype "passive"))
      (node (ref "Q7") (pin "2") (pinfunction "E_2") (pintype "passive"))
      (node (ref "R19") (pin "1") (pinfunction "1_1") (pintype "passive"))
      (node (ref "U1") (pin "2") (pinfunction "V-_2") (pintype "power_in"))
      (node (ref "U3") (pin "8") (pinfunction "Gnd_8") (pintype "power_in"))
    )
    (net (code "34") (name "Net-(C15-Pad2)") (class "Default")
      (node (ref "C15") (pin "2") (pinfunction "2_2") (pintype "passive"))
      (node (ref "R20") (pin "2") (pinfunction "2_2") (pintype "passive"))
      (node (ref "R23") (pin "2") (pinfunction "2_2") (pintype "passive"))
      (node (ref "U2") (pin "7") (pinfunction "7_7") (pintype "passive"))
      (node (ref "Z5") (pin "K") (pinfunction "K_K") (pintype "passive"))
    )
    (net (code "35") (name "Net-(D5-PadA)") (class "Default")
      (node (ref "D5") (pin "A") (pinfunction "A_A") (pintype "passive"))
      (node (ref "R9") (pin "1") (pinfunction "1_1") (pintype "passive"))
    )
    (net (code "36") (name "Net-(D6-PadA)") (class "Default")
      (node (ref "D6") (pin "A") (pinfunction "A_A") (pintype "passive"))
      (node (ref "R10") (pin "1") (pinfunction "1_1") (pintype "passive"))
    )
    (net (code "37") (name "Net-(D9-A1)") (class "Default")
      (node (ref "C15") (pin "1") (pinfunction "1_1") (pintype "passive"))
      (node (ref "D9") (pin "1") (pinfunction "A1_1") (pintype "passive"))
      (node (ref "D9") (pin "2") (pinfunction "A2_2") (pintype "passive"))
      (node (ref "R21") (pin "1") (pinfunction "1_1") (pintype "passive"))
      (node (ref "R23") (pin "1") (pinfunction "1_1") (pintype "passive"))
      (node (ref "U2") (pin "6") (pinfunction "B-_6") (pintype "passive"))
      (node (ref "Z5") (pin "A") (pinfunction "A_A") (pintype "passive"))
    )
    (net (code "38") (name "Net-(Q1A-G1)") (class "Default")
      (node (ref "Q1") (pin "2") (pinfunction "G1_2") (pintype "passive"))
      (node (ref "R2") (pin "1") (pinfunction "1_1") (pintype "passive"))
      (node (ref "R6") (pin "2") (pinfunction "2_2") (pintype "passive"))
      (node (ref "Z2") (pin "A") (pinfunction "A_A") (pintype "passive"))
    )
    (net (code "39") (name "Net-(Q1B-G2)") (class "Default")
      (node (ref "Q1") (pin "4") (pinfunction "G2_4") (pintype "passive"))
      (node (ref "R1") (pin "1") (pinfunction "1_1") (pintype "passive"))
      (node (ref "R5") (pin "2") (pinfunction "2_2") (pintype "passive"))
      (node (ref "Z1") (pin "A") (pinfunction "A_A") (pintype "passive"))
    )
    (net (code "40") (name "Net-(Q2A-G1)") (class "Default")
      (node (ref "Q2") (pin "2") (pinfunction "G1_2") (pintype "passive"))
      (node (ref "R4") (pin "1") (pinfunction "1_1") (pintype "passive"))
      (node (ref "R8") (pin "2") (pinfunction "2_2") (pintype "passive"))
      (node (ref "Z4") (pin "A") (pinfunction "A_A") (pintype "passive"))
    )
    (net (code "41") (name "Net-(Q2B-G2)") (class "Default")
      (node (ref "Q2") (pin "4") (pinfunction "G2_4") (pintype "passive"))
      (node (ref "R3") (pin "1") (pinfunction "1_1") (pintype "passive"))
      (node (ref "R7") (pin "2") (pinfunction "2_2") (pintype "passive"))
      (node (ref "Z3") (pin "A") (pinfunction "A_A") (pintype "passive"))
    )
    (net (code "42") (name "Net-(Q3-C1)") (class "Default")
      (node (ref "Q3") (pin "6") (pinfunction "C1_6") (pintype "passive"))
      (node (ref "R5") (pin "1") (pinfunction "1_1") (pintype "passive"))
    )
    (net (code "43") (name "Net-(Q4-B1)") (class "Default")
      (node (ref "Q4") (pin "2") (pinfunction "B1_2") (pintype "passive"))
      (node (ref "Q4") (pin "3") (pinfunction "C2_3") (pintype "passive"))
    )
    (net (code "44") (name "Net-(Q4-C1)") (class "Default")
      (node (ref "Q4") (pin "6") (pinfunction "C1_6") (pintype "passive"))
      (node (ref "R6") (pin "1") (pinfunction "1_1") (pintype "passive"))
    )
    (net (code "45") (name "Net-(Q5-C1)") (class "Default")
      (node (ref "Q5") (pin "6") (pinfunction "C1_6") (pintype "passive"))
      (node (ref "R7") (pin "1") (pinfunction "1_1") (pintype "passive"))
    )
    (net (code "46") (name "Net-(Q6-B1)") (class "Default")
      (node (ref "Q6") (pin "2") (pinfunction "B1_2") (pintype "passive"))
      (node (ref "Q6") (pin "3") (pinfunction "C2_3") (pintype "passive"))
    )
    (net (code "47") (name "Net-(Q6-C1)") (class "Default")
      (node (ref "Q6") (pin "6") (pinfunction "C1_6") (pintype "passive"))
      (node (ref "R8") (pin "1") (pinfunction "1_1") (pintype "passive"))
    )
    (net (code "48") (name "Net-(Q7-B)") (class "Default")
      (node (ref "Q7") (pin "1") (pinfunction "B_1") (pintype "passive"))
      (node (ref "R18") (pin "1") (pinfunction "1_1") (pintype "passive"))
    )
    (net (code "49") (name "Net-(Q8-D)") (class "Default")
      (node (ref "Q8") (pin "3") (pinfunction "D_3") (pintype "passive"))
      (node (ref "R30") (pin "2") (pinfunction "2_2") (pintype "passive"))
    )
    (net (code "50") (name "Net-(Q9-D)") (class "Default")
      (node (ref "Q9") (pin "3") (pinfunction "D_3") (pintype "passive"))
      (node (ref "R28") (pin "2") (pinfunction "2_2") (pintype "passive"))
    )
    (net (code "51") (name "Net-(Q10-D)") (class "Default")
      (node (ref "Q10") (pin "3") (pinfunction "D_3") (pintype "passive"))
      (node (ref "R31") (pin "2") (pinfunction "2_2") (pintype "passive"))
    )
    (net (code "52") (name "Net-(Q10-G)") (class "Default")
      (node (ref "Q10") (pin "1") (pinfunction "G_1") (pintype "passive"))
      (node (ref "Q11") (pin "1") (pinfunction "G_1") (pintype "passive"))
      (node (ref "Q7") (pin "3") (pinfunction "C_3") (pintype "passive"))
      (node (ref "Q8") (pin "1") (pinfunction "G_1") (pintype "passive"))
      (node (ref "Q9") (pin "1") (pinfunction "G_1") (pintype "passive"))
      (node (ref "R16") (pin "2") (pinfunction "2_2") (pintype "passive"))
      (node (ref "R19") (pin "2") (pinfunction "2_2") (pintype "passive"))
    )
    (net (code "53") (name "Net-(Q10-S)") (class "Default")
      (node (ref "C17") (pin "2") (pinfunction "2_2") (pintype "passive"))
      (node (ref "Q10") (pin "2") (pinfunction "S_2") (pintype "passive"))
      (node (ref "Q11") (pin "2") (pinfunction "S_2") (pintype "passive"))
      (node (ref "Q8") (pin "2") (pinfunction "S_2") (pintype "passive"))
      (node (ref "Q9") (pin "2") (pinfunction "S_2") (pintype "passive"))
      (node (ref "R22") (pin "2") (pinfunction "2_2") (pintype "passive"))
    )
    (net (code "54") (name "Net-(Q11-D)") (class "Default")
      (node (ref "Q11") (pin "3") (pinfunction "D_3") (pintype "passive"))
      (node (ref "R29") (pin "2") (pinfunction "2_2") (pintype "passive"))
    )
    (net (code "55") (name "Net-(Q12-D)") (class "Default")
      (node (ref "Q12") (pin "3") (pinfunction "D_3") (pintype "passive"))
      (node (ref "R25") (pin "2") (pinfunction "2_2") (pintype "passive"))
    )
    (net (code "56") (name "Net-(Q12-G)") (class "Default")
      (node (ref "Q12") (pin "1") (pinfunction "G_1") (pintype "passive"))
      (node (ref "Q13") (pin "3") (pinfunction "C_3") (pintype "passive"))
      (node (ref "R38") (pin "2") (pinfunction "2_2") (pintype "passive"))
    )
    (net (code "57") (name "Net-(Q13-B)") (class "Default")
      (node (ref "Q13") (pin "1") (pinfunction "B_1") (pintype "passive"))
      (node (ref "R33") (pin "1") (pinfunction "1_1") (pintype "passive"))
    )
    (net (code "58") (name "Net-(U1A-In+)") (class "Default")
      (node (ref "R11") (pin "1") (pinfunction "1_1") (pintype "passive"))
      (node (ref "U1") (pin "1") (pinfunction "In+_1") (pintype "passive"))
    )
    (net (code "59") (name "Net-(U1A-In-)") (class "Default")
      (node (ref "C10") (pin "1") (pinfunction "1_1") (pintype "passive"))
      (node (ref "R14") (pin "1") (pinfunction "1_1") (pintype "passive"))
      (node (ref "R15") (pin "1") (pinfunction "1_1") (pintype "passive"))
      (node (ref "U1") (pin "3") (pinfunction "In-_3") (pintype "passive"))
    )
    (net (code "60") (name "Net-(U2A-A-)") (class "Default")
      (node (ref "C16") (pin "1") (pinfunction "1_1") (pintype "passive"))
      (node (ref "R24") (pin "2") (pinfunction "2_2") (pintype "passive"))
      (node (ref "R25") (pin "1") (pinfunction "1_1") (pintype "passive"))
      (node (ref "R26") (pin "1") (pinfunction "1_1") (pintype "passive"))
      (node (ref "U2") (pin "2") (pinfunction "A-_2") (pintype "passive"))
    )
    (net (code "61") (name "Net-(U3-1Y0)") (class "Default")
      (node (ref "R32") (pin "1") (pinfunction "1_1") (pintype "passive"))
      (node (ref "U3") (pin "12") (pinfunction "1Y0_12") (pintype "passive"))
    )
    (net (code "62") (name "Net-(U3-1Y1)") (class "Default")
      (node (ref "R35") (pin "1") (pinfunction "1_1") (pintype "passive"))
      (node (ref "U3") (pin "14") (pinfunction "1Y1_14") (pintype "passive"))
    )
    (net (code "63") (name "Net-(U3-1Y2)") (class "Default")
      (node (ref "R34") (pin "1") (pinfunction "1_1") (pintype "passive"))
      (node (ref "U3") (pin "15") (pinfunction "1Y2_15") (pintype "passive"))
    )
    (net (code "64") (name "Net-(U3-1Y3)") (class "Default")
      (node (ref "R36") (pin "1") (pinfunction "1_1") (pintype "passive"))
      (node (ref "U3") (pin "11") (pinfunction "1Y3_11") (pintype "passive"))
    )
    (net (code "65") (name "Vnn") (class "Default")
      (node (ref "C9") (pin "2") (pinfunction "2_2") (pintype "passive"))
      (node (ref "R14") (pin "2") (pinfunction "2_2") (pintype "passive"))
      (node (ref "R17") (pin "1") (pinfunction "1_1") (pintype "passive"))
    )
    (net (code "66") (name "Vpp") (class "Default")
      (node (ref "Q1") (pin "1") (pinfunction "S1_1") (pintype "passive"))
      (node (ref "Q1") (pin "3") (pinfunction "S2_3") (pintype "passive"))
      (node (ref "Q2") (pin "1") (pinfunction "S1_1") (pintype "passive"))
      (node (ref "Q2") (pin "3") (pinfunction "S2_3") (pintype "passive"))
      (node (ref "R1") (pin "2") (pinfunction "2_2") (pintype "passive"))
      (node (ref "R2") (pin "2") (pinfunction "2_2") (pintype "passive"))
      (node (ref "R3") (pin "2") (pinfunction "2_2") (pintype "passive"))
      (node (ref "R4") (pin "2") (pinfunction "2_2") (pintype "passive"))
      (node (ref "Z1") (pin "K") (pinfunction "K_K") (pintype "passive"))
      (node (ref "Z2") (pin "K") (pinfunction "K_K") (pintype "passive"))
      (node (ref "Z3") (pin "K") (pinfunction "K_K") (pintype "passive"))
      (node (ref "Z4") (pin "K") (pinfunction "K_K") (pintype "passive"))
    )
    (net (code "67") (name "unconnected-(U3-2Y0-Pad1)") (class "Default")
      (node (ref "U3") (pin "1") (pinfunction "2Y0_1") (pintype "passive"))
    )
    (net (code "68") (name "unconnected-(U3-2Y1-Pad5)") (class "Default")
      (node (ref "U3") (pin "5") (pinfunction "2Y1_5") (pintype "passive"))
    )
    (net (code "69") (name "unconnected-(U3-2Y2-Pad2)") (class "Default")
      (node (ref "U3") (pin "2") (pinfunction "2Y2_2") (pintype "passive"))
    )
    (net (code "70") (name "unconnected-(U3-2Y3-Pad4)") (class "Default")
      (node (ref "U3") (pin "4") (pinfunction "2Y3_4") (pintype "passive"))
    )
    (net (code "71") (name "unconnected-(U3-2Z-Pad3)") (class "Default")
      (node (ref "U3") (pin "3") (pinfunction "2Z_3") (pintype "passive"))
    )
    (net (code "72") (name "unconnected-(Z5-PadNC)") (class "Default")
      (node (ref "Z5") (pin "NC") (pinfunction "NC_NC") (pintype "passive"))
    )
  )
)
